# BuzzerBaseShieldv12.net
KiCad netlist of a schematic drawn in EAGLE
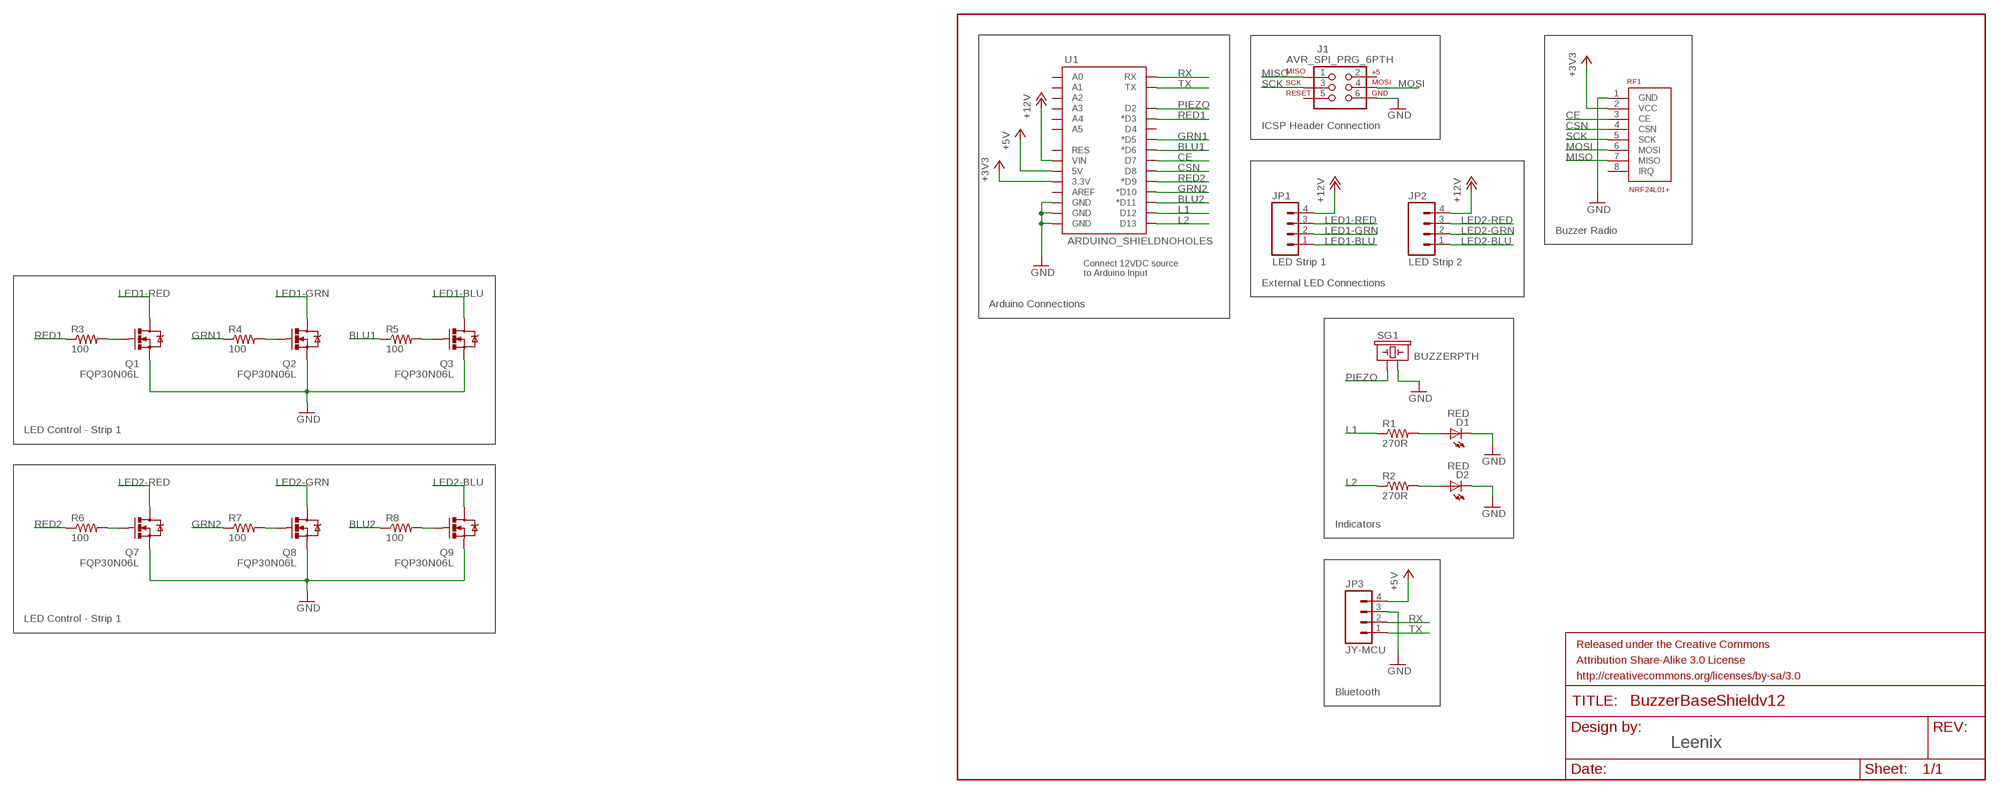
[diagram p0: schematic, sheet 1, part 1 of 2]
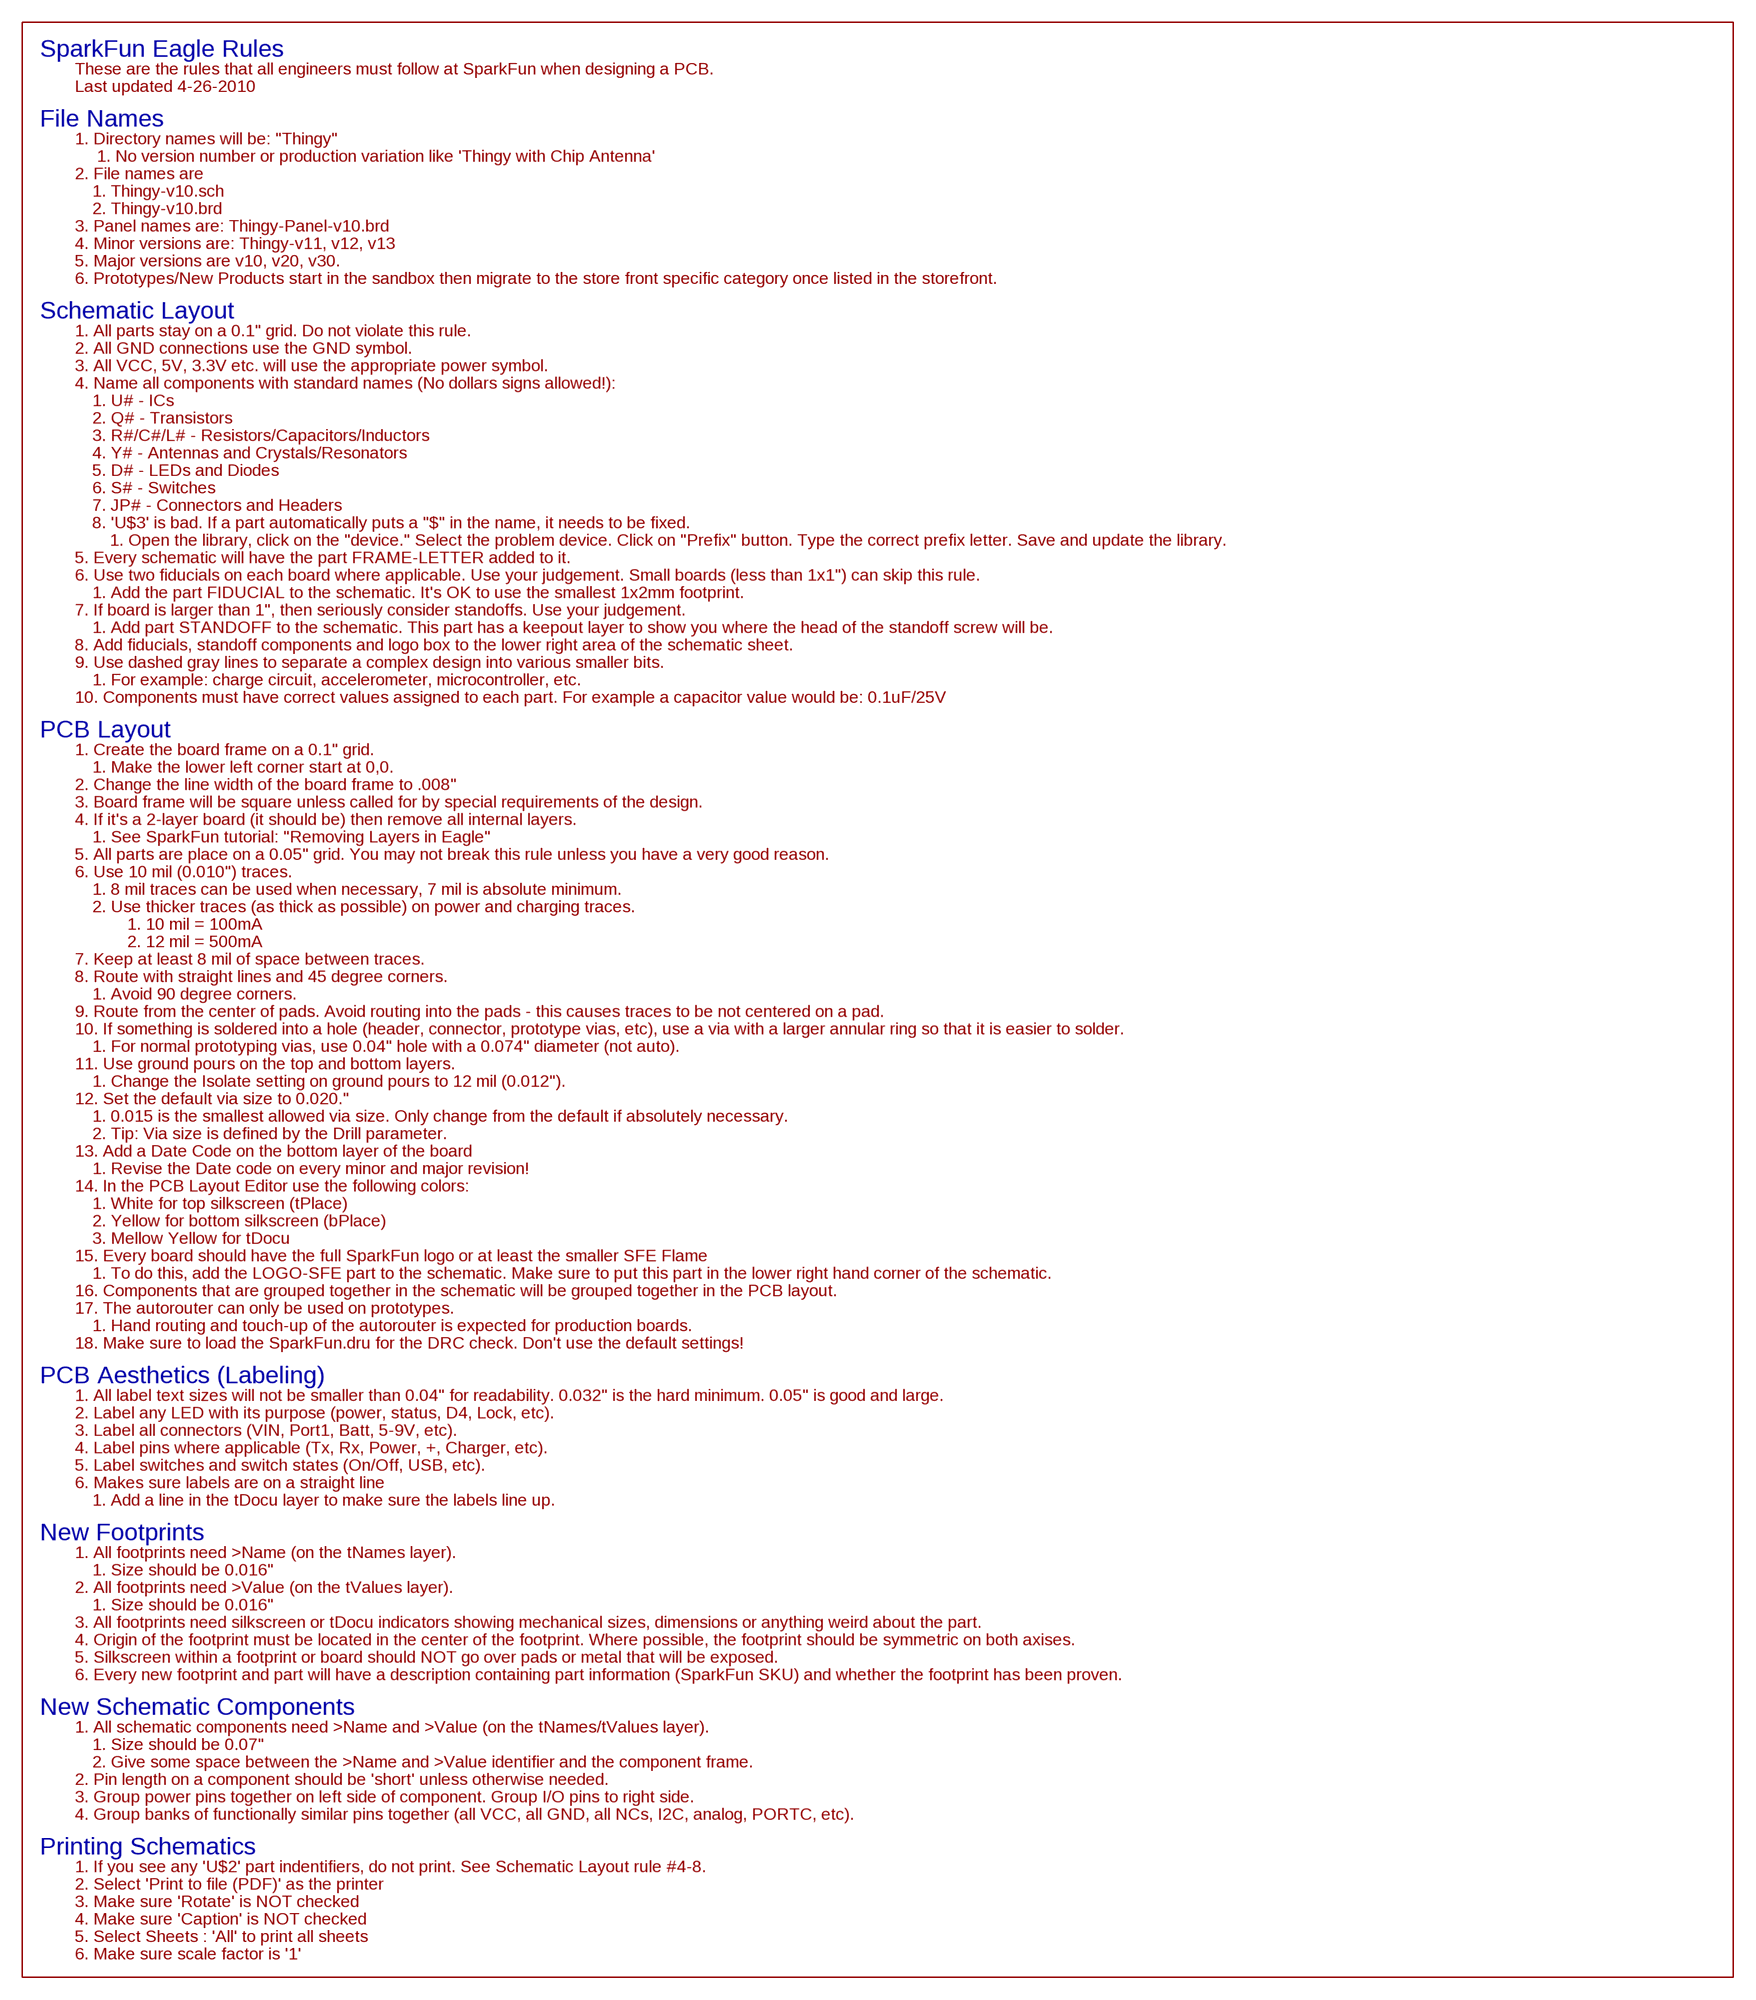
[diagram p1: schematic, sheet 1, part 2 of 2]

(export (version "E")
  (design (tool "Eeschema 10.0.6"))
  (components
    (comp (ref "D1")
      (value "RED")
      (footprint "eagle-import:LED-1206")
      (libsource (lib "eagle-import") (part "LED-RED1206"))
    )
    (comp (ref "D2")
      (value "RED")
      (footprint "eagle-import:LED-1206")
      (libsource (lib "eagle-import") (part "LED-RED1206"))
    )
    (comp (ref "FRAME1")
      (value "FRAME-LETTER")
      (footprint "eagle-import:CREATIVE_COMMONS")
      (libsource (lib "eagle-import") (part "FRAME-LETTER"))
    )
    (comp (ref "J1")
      (value "AVR_SPI_PRG_6PTH")
      (footprint "eagle-import:2X3")
      (libsource (lib "eagle-import") (part "AVR_SPI_PRG_6PTH"))
    )
    (comp (ref "JP1")
      (value "LED Strip 1")
      (footprint "eagle-import:1X04_LONGPADS")
      (libsource (lib "eagle-import") (part "M04LONGPADS"))
    )
    (comp (ref "JP2")
      (value "LED Strip 2")
      (footprint "eagle-import:1X04_LONGPADS")
      (libsource (lib "eagle-import") (part "M04LONGPADS"))
    )
    (comp (ref "JP3")
      (value "JY-MCU")
      (footprint "eagle-import:1X04_LONGPADS")
      (libsource (lib "eagle-import") (part "M04LONGPADS"))
    )
    (comp (ref "Q1")
      (value "FQP30N06L")
      (footprint "eagle-import:TO220V")
      (libsource (lib "eagle-import") (part "MOSFET-NCHANNELFQP30N06L"))
    )
    (comp (ref "Q2")
      (value "FQP30N06L")
      (footprint "eagle-import:TO220V")
      (libsource (lib "eagle-import") (part "MOSFET-NCHANNELFQP30N06L"))
    )
    (comp (ref "Q3")
      (value "FQP30N06L")
      (footprint "eagle-import:TO220V")
      (libsource (lib "eagle-import") (part "MOSFET-NCHANNELFQP30N06L"))
    )
    (comp (ref "Q7")
      (value "FQP30N06L")
      (footprint "eagle-import:TO220V")
      (libsource (lib "eagle-import") (part "MOSFET-NCHANNELFQP30N06L"))
    )
    (comp (ref "Q8")
      (value "FQP30N06L")
      (footprint "eagle-import:TO220V")
      (libsource (lib "eagle-import") (part "MOSFET-NCHANNELFQP30N06L"))
    )
    (comp (ref "Q9")
      (value "FQP30N06L")
      (footprint "eagle-import:TO220V")
      (libsource (lib "eagle-import") (part "MOSFET-NCHANNELFQP30N06L"))
    )
    (comp (ref "R1")
      (value "270R")
      (footprint "eagle-import:1206")
      (libsource (lib "eagle-import") (part "RESISTOR1206"))
    )
    (comp (ref "R2")
      (value "270R")
      (footprint "eagle-import:1206")
      (libsource (lib "eagle-import") (part "RESISTOR1206"))
    )
    (comp (ref "R3")
      (value "100")
      (footprint "eagle-import:1206")
      (libsource (lib "eagle-import") (part "RESISTOR1206"))
    )
    (comp (ref "R4")
      (value "100")
      (footprint "eagle-import:1206")
      (libsource (lib "eagle-import") (part "RESISTOR1206"))
    )
    (comp (ref "R5")
      (value "100")
      (footprint "eagle-import:1206")
      (libsource (lib "eagle-import") (part "RESISTOR1206"))
    )
    (comp (ref "R6")
      (value "100")
      (footprint "eagle-import:1206")
      (libsource (lib "eagle-import") (part "RESISTOR1206"))
    )
    (comp (ref "R7")
      (value "100")
      (footprint "eagle-import:1206")
      (libsource (lib "eagle-import") (part "RESISTOR1206"))
    )
    (comp (ref "R8")
      (value "100")
      (footprint "eagle-import:1206")
      (libsource (lib "eagle-import") (part "RESISTOR1206"))
    )
    (comp (ref "RF1")
      (value "NRF24L01+")
      (footprint "eagle-import:NRF24L01+-HEADER")
      (libsource (lib "eagle-import") (part "NRF24L01+"))
    )
    (comp (ref "SG1")
      (value "BUZZERPTH")
      (footprint "eagle-import:BUZZER-12MM")
      (libsource (lib "eagle-import") (part "BUZZERPTH"))
    )
    (comp (ref "U1")
      (value "ARDUINO_SHIELDNOHOLES")
      (footprint "eagle-import:DUEMILANOVE_SHIELD_NOHOLES")
      (libsource (lib "eagle-import") (part "ARDUINO_SHIELDNOHOLES"))
    )
  )
  (nets
    (net (code "1") (name "+3V3") (class "Default")
      (node (ref "RF1") (pin "2") (pinfunction "VCC_2") (pintype "power_in"))
      (node (ref "U1") (pin "3.3V") (pinfunction "3.3V_3.3V") (pintype "bidirectional"))
    )
    (net (code "2") (name "+5V") (class "Default")
      (node (ref "JP3") (pin "4") (pinfunction "4_4") (pintype "passive"))
      (node (ref "U1") (pin "5V") (pinfunction "5V_5V") (pintype "bidirectional"))
    )
    (net (code "3") (name "+12V") (class "Default")
      (node (ref "JP1") (pin "4") (pinfunction "4_4") (pintype "passive"))
      (node (ref "JP2") (pin "4") (pinfunction "4_4") (pintype "passive"))
      (node (ref "U1") (pin "VIN") (pinfunction "VIN_VIN") (pintype "bidirectional"))
    )
    (net (code "4") (name "/BLU1") (class "Default")
      (node (ref "R5") (pin "1") (pinfunction "1_1") (pintype "passive"))
      (node (ref "U1") (pin "D6") (pinfunction "*D6_D6") (pintype "bidirectional"))
    )
    (net (code "5") (name "/BLU2") (class "Default")
      (node (ref "R8") (pin "1") (pinfunction "1_1") (pintype "passive"))
      (node (ref "U1") (pin "D11") (pinfunction "*D11_D11") (pintype "bidirectional"))
    )
    (net (code "6") (name "/CE") (class "Default")
      (node (ref "RF1") (pin "3") (pinfunction "CE_3") (pintype "bidirectional"))
      (node (ref "U1") (pin "D7") (pinfunction "D7_D7") (pintype "bidirectional"))
    )
    (net (code "7") (name "/CSN") (class "Default")
      (node (ref "RF1") (pin "4") (pinfunction "CSN_4") (pintype "bidirectional"))
      (node (ref "U1") (pin "D8") (pinfunction "D8_D8") (pintype "bidirectional"))
    )
    (net (code "8") (name "/GRN1") (class "Default")
      (node (ref "R4") (pin "1") (pinfunction "1_1") (pintype "passive"))
      (node (ref "U1") (pin "D5") (pinfunction "*D5_D5") (pintype "bidirectional"))
    )
    (net (code "9") (name "/GRN2") (class "Default")
      (node (ref "R7") (pin "1") (pinfunction "1_1") (pintype "passive"))
      (node (ref "U1") (pin "D10") (pinfunction "*D10_D10") (pintype "bidirectional"))
    )
    (net (code "10") (name "/L1") (class "Default")
      (node (ref "R1") (pin "1") (pinfunction "1_1") (pintype "passive"))
      (node (ref "U1") (pin "D12") (pinfunction "D12_D12") (pintype "bidirectional"))
    )
    (net (code "11") (name "/L2") (class "Default")
      (node (ref "R2") (pin "1") (pinfunction "1_1") (pintype "passive"))
      (node (ref "U1") (pin "D13") (pinfunction "D13_D13") (pintype "bidirectional"))
    )
    (net (code "12") (name "/LED1-BLU") (class "Default")
      (node (ref "JP1") (pin "1") (pinfunction "1_1") (pintype "passive"))
      (node (ref "Q3") (pin "2") (pinfunction "D_2") (pintype "passive"))
    )
    (net (code "13") (name "/LED1-GRN") (class "Default")
      (node (ref "JP1") (pin "2") (pinfunction "2_2") (pintype "passive"))
      (node (ref "Q2") (pin "2") (pinfunction "D_2") (pintype "passive"))
    )
    (net (code "14") (name "/LED1-RED") (class "Default")
      (node (ref "JP1") (pin "3") (pinfunction "3_3") (pintype "passive"))
      (node (ref "Q1") (pin "2") (pinfunction "D_2") (pintype "passive"))
    )
    (net (code "15") (name "/LED2-BLU") (class "Default")
      (node (ref "JP2") (pin "1") (pinfunction "1_1") (pintype "passive"))
      (node (ref "Q9") (pin "2") (pinfunction "D_2") (pintype "passive"))
    )
    (net (code "16") (name "/LED2-GRN") (class "Default")
      (node (ref "JP2") (pin "2") (pinfunction "2_2") (pintype "passive"))
      (node (ref "Q8") (pin "2") (pinfunction "D_2") (pintype "passive"))
    )
    (net (code "17") (name "/LED2-RED") (class "Default")
      (node (ref "JP2") (pin "3") (pinfunction "3_3") (pintype "passive"))
      (node (ref "Q7") (pin "2") (pinfunction "D_2") (pintype "passive"))
    )
    (net (code "18") (name "/MISO") (class "Default")
      (node (ref "J1") (pin "1") (pinfunction "1_1") (pintype "passive"))
      (node (ref "RF1") (pin "7") (pinfunction "MISO_7") (pintype "bidirectional"))
    )
    (net (code "19") (name "/MOSI") (class "Default")
      (node (ref "J1") (pin "4") (pinfunction "4_4") (pintype "passive"))
      (node (ref "RF1") (pin "6") (pinfunction "MOSI_6") (pintype "bidirectional"))
    )
    (net (code "20") (name "/PIEZO") (class "Default")
      (node (ref "SG1") (pin "+") (pinfunction "1_+") (pintype "passive"))
      (node (ref "U1") (pin "D2") (pinfunction "D2_D2") (pintype "bidirectional"))
    )
    (net (code "21") (name "/RED1") (class "Default")
      (node (ref "R3") (pin "1") (pinfunction "1_1") (pintype "passive"))
      (node (ref "U1") (pin "D3") (pinfunction "*D3_D3") (pintype "bidirectional"))
    )
    (net (code "22") (name "/RED2") (class "Default")
      (node (ref "R6") (pin "1") (pinfunction "1_1") (pintype "passive"))
      (node (ref "U1") (pin "D9") (pinfunction "*D9_D9") (pintype "bidirectional"))
    )
    (net (code "23") (name "/RX") (class "Default")
      (node (ref "JP3") (pin "2") (pinfunction "2_2") (pintype "passive"))
      (node (ref "U1") (pin "RX") (pinfunction "RX_RX") (pintype "bidirectional"))
    )
    (net (code "24") (name "/SCK") (class "Default")
      (node (ref "J1") (pin "3") (pinfunction "3_3") (pintype "passive"))
      (node (ref "RF1") (pin "5") (pinfunction "SCK_5") (pintype "bidirectional"))
    )
    (net (code "25") (name "/TX") (class "Default")
      (node (ref "JP3") (pin "1") (pinfunction "1_1") (pintype "passive"))
      (node (ref "U1") (pin "TX") (pinfunction "TX_TX") (pintype "bidirectional"))
    )
    (net (code "26") (name "GND") (class "Default")
      (node (ref "D1") (pin "C") (pinfunction "C_C") (pintype "passive"))
      (node (ref "D2") (pin "C") (pinfunction "C_C") (pintype "passive"))
      (node (ref "J1") (pin "6") (pinfunction "6_6") (pintype "passive"))
      (node (ref "JP3") (pin "3") (pinfunction "3_3") (pintype "passive"))
      (node (ref "Q1") (pin "3") (pinfunction "S_3") (pintype "passive"))
      (node (ref "Q2") (pin "3") (pinfunction "S_3") (pintype "passive"))
      (node (ref "Q3") (pin "3") (pinfunction "S_3") (pintype "passive"))
      (node (ref "Q7") (pin "3") (pinfunction "S_3") (pintype "passive"))
      (node (ref "Q8") (pin "3") (pinfunction "S_3") (pintype "passive"))
      (node (ref "Q9") (pin "3") (pinfunction "S_3") (pintype "passive"))
      (node (ref "RF1") (pin "1") (pinfunction "GND_1") (pintype "power_in"))
      (node (ref "SG1") (pin "-") (pinfunction "2_-") (pintype "passive"))
      (node (ref "U1") (pin "GND@0") (pinfunction "GND_GND@0") (pintype "bidirectional"))
      (node (ref "U1") (pin "GND@1") (pinfunction "GND_GND@1") (pintype "bidirectional"))
      (node (ref "U1") (pin "GND@2") (pinfunction "GND_GND@2") (pintype "bidirectional"))
    )
    (net (code "27") (name "Net-(D1-PadA)") (class "Default")
      (node (ref "D1") (pin "A") (pinfunction "A_A") (pintype "passive"))
      (node (ref "R1") (pin "2") (pinfunction "2_2") (pintype "passive"))
    )
    (net (code "28") (name "Net-(D2-PadA)") (class "Default")
      (node (ref "D2") (pin "A") (pinfunction "A_A") (pintype "passive"))
      (node (ref "R2") (pin "2") (pinfunction "2_2") (pintype "passive"))
    )
    (net (code "29") (name "Net-(Q1-G)") (class "Default")
      (node (ref "Q1") (pin "1") (pinfunction "G_1") (pintype "passive"))
      (node (ref "R3") (pin "2") (pinfunction "2_2") (pintype "passive"))
    )
    (net (code "30") (name "Net-(Q2-G)") (class "Default")
      (node (ref "Q2") (pin "1") (pinfunction "G_1") (pintype "passive"))
      (node (ref "R4") (pin "2") (pinfunction "2_2") (pintype "passive"))
    )
    (net (code "31") (name "Net-(Q3-G)") (class "Default")
      (node (ref "Q3") (pin "1") (pinfunction "G_1") (pintype "passive"))
      (node (ref "R5") (pin "2") (pinfunction "2_2") (pintype "passive"))
    )
    (net (code "32") (name "Net-(Q7-G)") (class "Default")
      (node (ref "Q7") (pin "1") (pinfunction "G_1") (pintype "passive"))
      (node (ref "R6") (pin "2") (pinfunction "2_2") (pintype "passive"))
    )
    (net (code "33") (name "Net-(Q8-G)") (class "Default")
      (node (ref "Q8") (pin "1") (pinfunction "G_1") (pintype "passive"))
      (node (ref "R7") (pin "2") (pinfunction "2_2") (pintype "passive"))
    )
    (net (code "34") (name "Net-(Q9-G)") (class "Default")
      (node (ref "Q9") (pin "1") (pinfunction "G_1") (pintype "passive"))
      (node (ref "R8") (pin "2") (pinfunction "2_2") (pintype "passive"))
    )
    (net (code "35") (name "unconnected-(J1-Pad2)") (class "Default")
      (node (ref "J1") (pin "2") (pinfunction "2_2") (pintype "passive"))
    )
    (net (code "36") (name "unconnected-(J1-Pad5)") (class "Default")
      (node (ref "J1") (pin "5") (pinfunction "5_5") (pintype "passive"))
    )
    (net (code "37") (name "unconnected-(RF1-IRQ-Pad8)") (class "Default")
      (node (ref "RF1") (pin "8") (pinfunction "IRQ_8") (pintype "bidirectional"))
    )
    (net (code "38") (name "unconnected-(U1-PadA0)") (class "Default")
      (node (ref "U1") (pin "A0") (pinfunction "A0_A0") (pintype "bidirectional"))
    )
    (net (code "39") (name "unconnected-(U1-PadA1)") (class "Default")
      (node (ref "U1") (pin "A1") (pinfunction "A1_A1") (pintype "bidirectional"))
    )
    (net (code "40") (name "unconnected-(U1-PadA2)") (class "Default")
      (node (ref "U1") (pin "A2") (pinfunction "A2_A2") (pintype "bidirectional"))
    )
    (net (code "41") (name "unconnected-(U1-PadA3)") (class "Default")
      (node (ref "U1") (pin "A3") (pinfunction "A3_A3") (pintype "bidirectional"))
    )
    (net (code "42") (name "unconnected-(U1-PadA4)") (class "Default")
      (node (ref "U1") (pin "A4") (pinfunction "A4_A4") (pintype "bidirectional"))
    )
    (net (code "43") (name "unconnected-(U1-PadA5)") (class "Default")
      (node (ref "U1") (pin "A5") (pinfunction "A5_A5") (pintype "bidirectional"))
    )
    (net (code "44") (name "unconnected-(U1-PadAREF)") (class "Default")
      (node (ref "U1") (pin "AREF") (pinfunction "AREF_AREF") (pintype "bidirectional"))
    )
    (net (code "45") (name "unconnected-(U1-PadD4)") (class "Default")
      (node (ref "U1") (pin "D4") (pinfunction "D4_D4") (pintype "bidirectional"))
    )
    (net (code "46") (name "unconnected-(U1-PadRES)") (class "Default")
      (node (ref "U1") (pin "RES") (pinfunction "RES_RES") (pintype "bidirectional"))
    )
  )
)
